# Sheet_2.net
KiCad netlist of a schematic drawn in Altium Designer
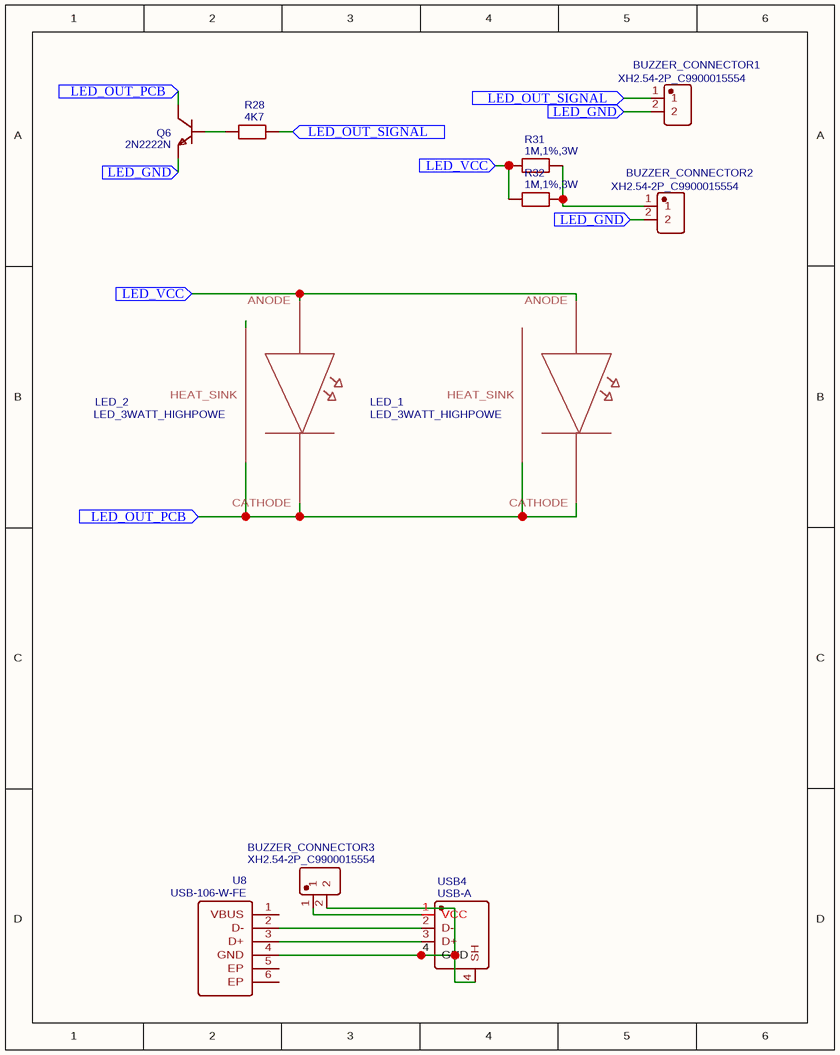
[diagram p0: Sheet_2.schdoc]

(export (version "E")
  (design (tool "Eeschema 10.0.6"))
  (components
    (comp (ref "BUZZER_CONNECTOR1")
      (value "XH2.54-2P_C9900015554")
      (fields (field (name "MANUFACTURER PART") "XH2.54-2P") (field (name "CONTRIBUTOR") "lcsc"))
      (libsource (lib "altium-import") (part "root_0_XH2.54-2P_C9900015554_"))
    )
    (comp (ref "BUZZER_CONNECTOR2")
      (value "XH2.54-2P_C9900015554")
      (fields (field (name "MANUFACTURER PART") "XH2.54-2P") (field (name "CONTRIBUTOR") "lcsc"))
      (libsource (lib "altium-import") (part "root_0_XH2.54-2P_C9900015554_"))
    )
    (comp (ref "BUZZER_CONNECTOR3")
      (value "XH2.54-2P_C9900015554")
      (fields (field (name "MANUFACTURER PART") "XH2.54-2P") (field (name "CONTRIBUTOR") "lcsc"))
      (libsource (lib "altium-import") (part "root_1_XH2.54-2P_C9900015554_"))
    )
    (comp (ref "LED_1")
      (value "LED_3WATT_HIGHPOWE")
      (fields (field (name "CONTRIBUTOR") "vikalpvs"))
      (libsource (lib "altium-import") (part "root_3_LED_3WATT_HIGHPOWE_"))
    )
    (comp (ref "LED_2")
      (value "LED_3WATT_HIGHPOWE")
      (fields (field (name "CONTRIBUTOR") "vikalpvs"))
      (libsource (lib "altium-import") (part "root_3_LED_3WATT_HIGHPOWE_"))
    )
    (comp (ref "Q6")
      (value "2N2222N")
      (fields
        (field (name "MANUFACTURER") "BLUE ROCKET(蓝箭)")
        (field (name "MANUFACTURER PART") "2N2222A")
        (field (name "CONTRIBUTOR") "Lee Smith")
      )
      (libsource (lib "altium-import") (part "root_0_2N2222N_"))
    )
    (comp (ref "R28")
      (value "4K7")
      (fields (field (name "CONTRIBUTOR") "canarywood"))
      (libsource (lib "altium-import") (part "root_3_4K7_"))
    )
    (comp (ref "R31")
      (value "1M,1%,3W")
      (fields
        (field (name "MANUFACTURER") "Ohmite")
        (field (name "MANUFACTURER PART") "MOX1125231005G")
        (field (name "CONTRIBUTOR") "NavinL")
      )
      (libsource (lib "altium-import") (part "root_3_1M,1%,3W_"))
    )
    (comp (ref "R32")
      (value "1M,1%,3W")
      (fields
        (field (name "MANUFACTURER") "Ohmite")
        (field (name "MANUFACTURER PART") "MOX1125231005G")
        (field (name "CONTRIBUTOR") "NavinL")
      )
      (libsource (lib "altium-import") (part "root_3_1M,1%,3W_"))
    )
    (comp (ref "U8")
      (value "USB-106-W-FE")
      (fields (field (name "MANUFACTURER") "HOOYA(皓宇电子)") (field (name "CONTRIBUTOR") "lcsc"))
      (libsource (lib "altium-import") (part "root_0_USB-106-W-FE_"))
    )
    (comp (ref "USB4")
      (value "USB-A")
      (fields (field (name "CONTRIBUTOR") "LCSC"))
      (libsource (lib "altium-import") (part "root_0_USB-A_"))
    )
  )
  (nets
    (net (code "1") (name "/LED_GND") (class "Default")
      (node (ref "BUZZER_CONNECTOR1") (pin "2") (pinfunction "2_2") (pintype "passive"))
      (node (ref "BUZZER_CONNECTOR2") (pin "2") (pinfunction "2_2") (pintype "passive"))
      (node (ref "Q6") (pin "1") (pinfunction "E_1") (pintype "passive"))
    )
    (net (code "2") (name "/LED_OUT_PCB") (class "Default")
      (node (ref "LED_1") (pin "P$2") (pinfunction "CATHODE_P$2") (pintype "passive"))
      (node (ref "LED_2") (pin "P$2") (pinfunction "CATHODE_P$2") (pintype "passive"))
      (node (ref "Q6") (pin "3") (pinfunction "C_3") (pintype "passive"))
    )
    (net (code "3") (name "/LED_OUT_SIGNAL") (class "Default")
      (node (ref "BUZZER_CONNECTOR1") (pin "1") (pinfunction "1_1") (pintype "passive"))
      (node (ref "R28") (pin "2") (pinfunction "2_2") (pintype "passive"))
    )
    (net (code "4") (name "/LED_VCC") (class "Default")
      (node (ref "LED_1") (pin "P$1") (pinfunction "ANODE_P$1") (pintype "passive"))
      (node (ref "LED_2") (pin "P$1") (pinfunction "ANODE_P$1") (pintype "passive"))
      (node (ref "R31") (pin "1") (pinfunction "1_1") (pintype "passive"))
      (node (ref "R32") (pin "1") (pinfunction "1_1") (pintype "passive"))
    )
    (net (code "5") (name "Net-(BUZZER_CONNECTOR2-Pad1)") (class "Default")
      (node (ref "BUZZER_CONNECTOR2") (pin "1") (pinfunction "1_1") (pintype "passive"))
      (node (ref "R31") (pin "2") (pinfunction "2_2") (pintype "passive"))
      (node (ref "R32") (pin "2") (pinfunction "2_2") (pintype "passive"))
    )
    (net (code "6") (name "Net-(Q6-B)") (class "Default")
      (node (ref "Q6") (pin "2") (pinfunction "B_2") (pintype "passive"))
      (node (ref "R28") (pin "1") (pinfunction "1_1") (pintype "passive"))
    )
    (net (code "7") (name "Net-(U8-D+)") (class "Default")
      (node (ref "U8") (pin "3") (pinfunction "D+_3") (pintype "passive"))
      (node (ref "USB4") (pin "3") (pinfunction "D+_3") (pintype "passive"))
    )
    (net (code "8") (name "Net-(U8-D-)") (class "Default")
      (node (ref "U8") (pin "2") (pinfunction "D-_2") (pintype "passive"))
      (node (ref "USB4") (pin "2") (pinfunction "D-_2") (pintype "passive"))
    )
    (net (code "9") (name "Net-(U8-GND)") (class "Default")
      (node (ref "BUZZER_CONNECTOR3") (pin "2") (pinfunction "2_2") (pintype "passive"))
      (node (ref "U8") (pin "4") (pinfunction "GND_4") (pintype "passive"))
      (node (ref "USB4") (pin "4") (pinfunction "GND_4") (pintype "passive"))
    )
    (net (code "10") (name "Net-(USB4-VCC)") (class "Default")
      (node (ref "BUZZER_CONNECTOR3") (pin "1") (pinfunction "1_1") (pintype "passive"))
      (node (ref "USB4") (pin "1") (pinfunction "VCC_1") (pintype "passive"))
    )
    (net (code "11") (name "unconnected-(LED_1-HEAT_SINK-PadP$3)") (class "Default")
      (node (ref "LED_1") (pin "P$3") (pinfunction "HEAT_SINK_P$3") (pintype "passive"))
    )
    (net (code "12") (name "unconnected-(LED_2-HEAT_SINK-PadP$3)") (class "Default")
      (node (ref "LED_2") (pin "P$3") (pinfunction "HEAT_SINK_P$3") (pintype "passive"))
    )
    (net (code "13") (name "unconnected-(U8-EP-Pad5)") (class "Default")
      (node (ref "U8") (pin "5") (pinfunction "EP_5") (pintype "passive"))
    )
    (net (code "14") (name "unconnected-(U8-EP-Pad6)") (class "Default")
      (node (ref "U8") (pin "6") (pinfunction "EP_6") (pintype "passive"))
    )
    (net (code "15") (name "unconnected-(U8-VBUS-Pad1)") (class "Default")
      (node (ref "U8") (pin "1") (pinfunction "VBUS_1") (pintype "passive"))
    )
  )
)
